# Solar_Lantern.net
KiCad netlist of a schematic drawn in EAGLE
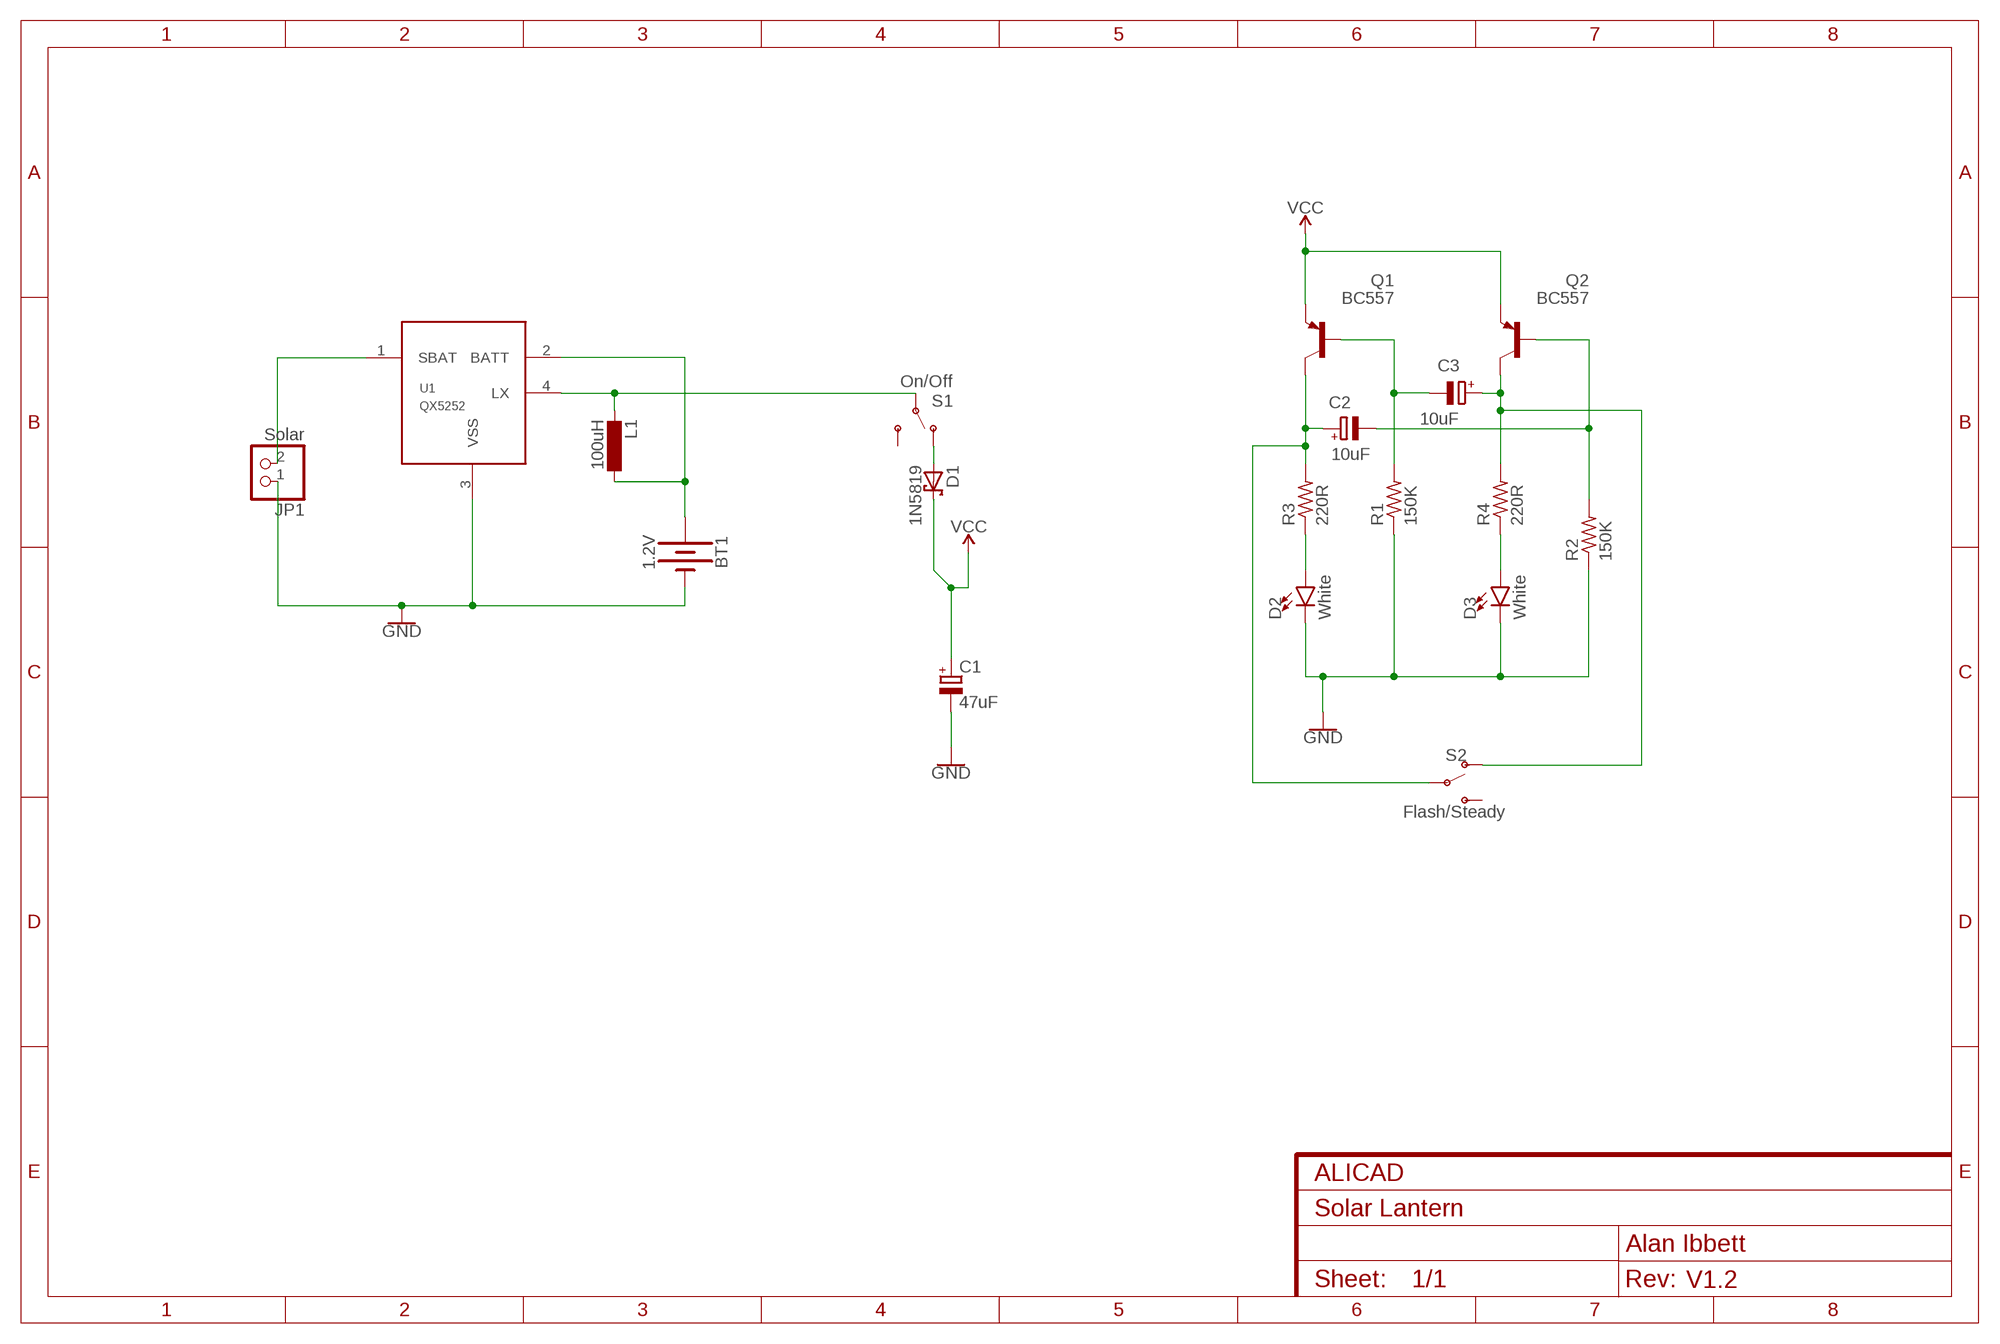
[diagram p0: schematic, sheet 1]

(export (version "E")
  (design (tool "Eeschema 10.0.6"))
  (components
    (comp (ref "BT1")
      (value "1.2V")
      (footprint "eagle-import:BATTERY-AA")
      (libsource (lib "eagle-import") (part "BATTERY-AA"))
    )
    (comp (ref "C1")
      (value "47uF")
      (footprint "eagle-import:E3,5-8")
      (libsource (lib "eagle-import") (part "CPOL-EUE3.5-8"))
    )
    (comp (ref "C2")
      (value "10uF")
      (footprint "eagle-import:E2,5-7")
      (libsource (lib "eagle-import") (part "CPOL-EUE2.5-7"))
    )
    (comp (ref "C3")
      (value "10uF")
      (footprint "eagle-import:E2,5-7")
      (libsource (lib "eagle-import") (part "CPOL-EUE2.5-7"))
    )
    (comp (ref "D1")
      (value "1N5819")
      (footprint "eagle-import:DO35-7")
      (libsource (lib "eagle-import") (part "SCHOTTKY-DIODEDO35-7"))
    )
    (comp (ref "D2")
      (value "White")
      (footprint "eagle-import:LED_5MM")
      (libsource (lib "eagle-import") (part "LED5MM"))
    )
    (comp (ref "D3")
      (value "White")
      (footprint "eagle-import:LED_5MM")
      (libsource (lib "eagle-import") (part "LED5MM"))
    )
    (comp (ref "JP1")
      (value "Solar")
      (footprint "eagle-import:1X02")
      (libsource (lib "eagle-import") (part "PINHD-1X2"))
    )
    (comp (ref "L1")
      (value "100uH")
      (footprint "eagle-import:0207_10")
      (libsource (lib "eagle-import") (part "L-EU0207/10"))
    )
    (comp (ref "Q1")
      (value "BC557")
      (footprint "eagle-import:TO92")
      (libsource (lib "eagle-import") (part "BC557"))
    )
    (comp (ref "Q2")
      (value "BC557")
      (footprint "eagle-import:TO92")
      (libsource (lib "eagle-import") (part "BC557"))
    )
    (comp (ref "R1")
      (value "150K")
      (footprint "eagle-import:0207_10")
      (libsource (lib "eagle-import") (part "R-US_0207/10"))
    )
    (comp (ref "R2")
      (value "150K")
      (footprint "eagle-import:0207_10")
      (libsource (lib "eagle-import") (part "R-US_0207/10"))
    )
    (comp (ref "R3")
      (value "220R")
      (footprint "eagle-import:0207_10")
      (libsource (lib "eagle-import") (part "R-US_0207/10"))
    )
    (comp (ref "R4")
      (value "220R")
      (footprint "eagle-import:0207_10")
      (libsource (lib "eagle-import") (part "R-US_0207/10"))
    )
    (comp (ref "S1")
      (value "On/Off")
      (footprint "eagle-import:SWITCH_SPDT_PTH_11.6X4.0MM")
      (libsource (lib "eagle-import") (part "SWITCH-SPDT-PTH-11.6X4.0MM"))
    )
    (comp (ref "S2")
      (value "Flash/Steady")
      (footprint "eagle-import:SWITCH_SPDT_PTH_11.6X4.0MM")
      (libsource (lib "eagle-import") (part "SWITCH-SPDT-PTH-11.6X4.0MM"))
    )
    (comp (ref "U1")
      (value "QX5252")
      (footprint "eagle-import:TO94")
      (libsource (lib "eagle-import") (part "QX5252"))
    )
  )
  (nets
    (net (code "1") (name "GND") (class "Default")
      (node (ref "BT1") (pin "GND@1") (pinfunction "-_GND@1") (pintype "power_in"))
      (node (ref "C1") (pin "-") (pinfunction "-_-") (pintype "passive"))
      (node (ref "D2") (pin "K") (pinfunction "C_K") (pintype "passive"))
      (node (ref "D3") (pin "K") (pinfunction "C_K") (pintype "passive"))
      (node (ref "JP1") (pin "1") (pinfunction "1_1") (pintype "passive"))
      (node (ref "R1") (pin "1") (pinfunction "1_1") (pintype "passive"))
      (node (ref "R2") (pin "1") (pinfunction "1_1") (pintype "passive"))
      (node (ref "U1") (pin "3") (pinfunction "VSS_3") (pintype "power_in"))
    )
    (net (code "2") (name "Net-(BT1-+)") (class "Default")
      (node (ref "BT1") (pin "PWR@1") (pinfunction "+_PWR@1") (pintype "power_in"))
      (node (ref "L1") (pin "1") (pinfunction "1_1") (pintype "passive"))
      (node (ref "U1") (pin "2") (pinfunction "BATT_2") (pintype "bidirectional"))
    )
    (net (code "3") (name "Net-(D2-PadA)") (class "Default")
      (node (ref "D2") (pin "A") (pinfunction "A_A") (pintype "passive"))
      (node (ref "R3") (pin "1") (pinfunction "1_1") (pintype "passive"))
    )
    (net (code "4") (name "Net-(D3-PadA)") (class "Default")
      (node (ref "D3") (pin "A") (pinfunction "A_A") (pintype "passive"))
      (node (ref "R4") (pin "1") (pinfunction "1_1") (pintype "passive"))
    )
    (net (code "5") (name "Net-(Q1-B)") (class "Default")
      (node (ref "C3") (pin "-") (pinfunction "-_-") (pintype "passive"))
      (node (ref "Q1") (pin "2") (pinfunction "B_2") (pintype "passive"))
      (node (ref "R1") (pin "2") (pinfunction "2_2") (pintype "passive"))
    )
    (net (code "6") (name "Net-(Q1-C)") (class "Default")
      (node (ref "C2") (pin "+") (pinfunction "+_+") (pintype "passive"))
      (node (ref "Q1") (pin "3") (pinfunction "C_3") (pintype "passive"))
      (node (ref "R3") (pin "2") (pinfunction "2_2") (pintype "passive"))
      (node (ref "S2") (pin "2") (pinfunction "P_2") (pintype "passive"))
    )
    (net (code "7") (name "Net-(Q2-B)") (class "Default")
      (node (ref "C2") (pin "-") (pinfunction "-_-") (pintype "passive"))
      (node (ref "Q2") (pin "2") (pinfunction "B_2") (pintype "passive"))
      (node (ref "R2") (pin "2") (pinfunction "2_2") (pintype "passive"))
    )
    (net (code "8") (name "Net-(Q2-C)") (class "Default")
      (node (ref "C3") (pin "+") (pinfunction "+_+") (pintype "passive"))
      (node (ref "Q2") (pin "3") (pinfunction "C_3") (pintype "passive"))
      (node (ref "R4") (pin "2") (pinfunction "2_2") (pintype "passive"))
      (node (ref "S2") (pin "1") (pinfunction "O_1") (pintype "passive"))
    )
    (net (code "9") (name "Net-(S1-O)") (class "Default")
      (node (ref "D1") (pin "A") (pinfunction "A_A") (pintype "passive"))
      (node (ref "S1") (pin "1") (pinfunction "O_1") (pintype "passive"))
    )
    (net (code "10") (name "Net-(S1-P)") (class "Default")
      (node (ref "L1") (pin "2") (pinfunction "2_2") (pintype "passive"))
      (node (ref "S1") (pin "2") (pinfunction "P_2") (pintype "passive"))
      (node (ref "U1") (pin "4") (pinfunction "LX_4") (pintype "bidirectional"))
    )
    (net (code "11") (name "Net-(U1-SBAT)") (class "Default")
      (node (ref "JP1") (pin "2") (pinfunction "2_2") (pintype "passive"))
      (node (ref "U1") (pin "1") (pinfunction "SBAT_1") (pintype "bidirectional"))
    )
    (net (code "12") (name "VCC") (class "Default")
      (node (ref "C1") (pin "+") (pinfunction "+_+") (pintype "passive"))
      (node (ref "D1") (pin "C") (pinfunction "C_C") (pintype "passive"))
      (node (ref "Q1") (pin "1") (pinfunction "E_1") (pintype "passive"))
      (node (ref "Q2") (pin "1") (pinfunction "E_1") (pintype "passive"))
    )
    (net (code "13") (name "unconnected-(S1-S-Pad3)") (class "Default")
      (node (ref "S1") (pin "3") (pinfunction "S_3") (pintype "passive"))
    )
    (net (code "14") (name "unconnected-(S2-S-Pad3)") (class "Default")
      (node (ref "S2") (pin "3") (pinfunction "S_3") (pintype "passive"))
    )
  )
)
